# module.net
KiCad netlist of a schematic drawn in EAGLE
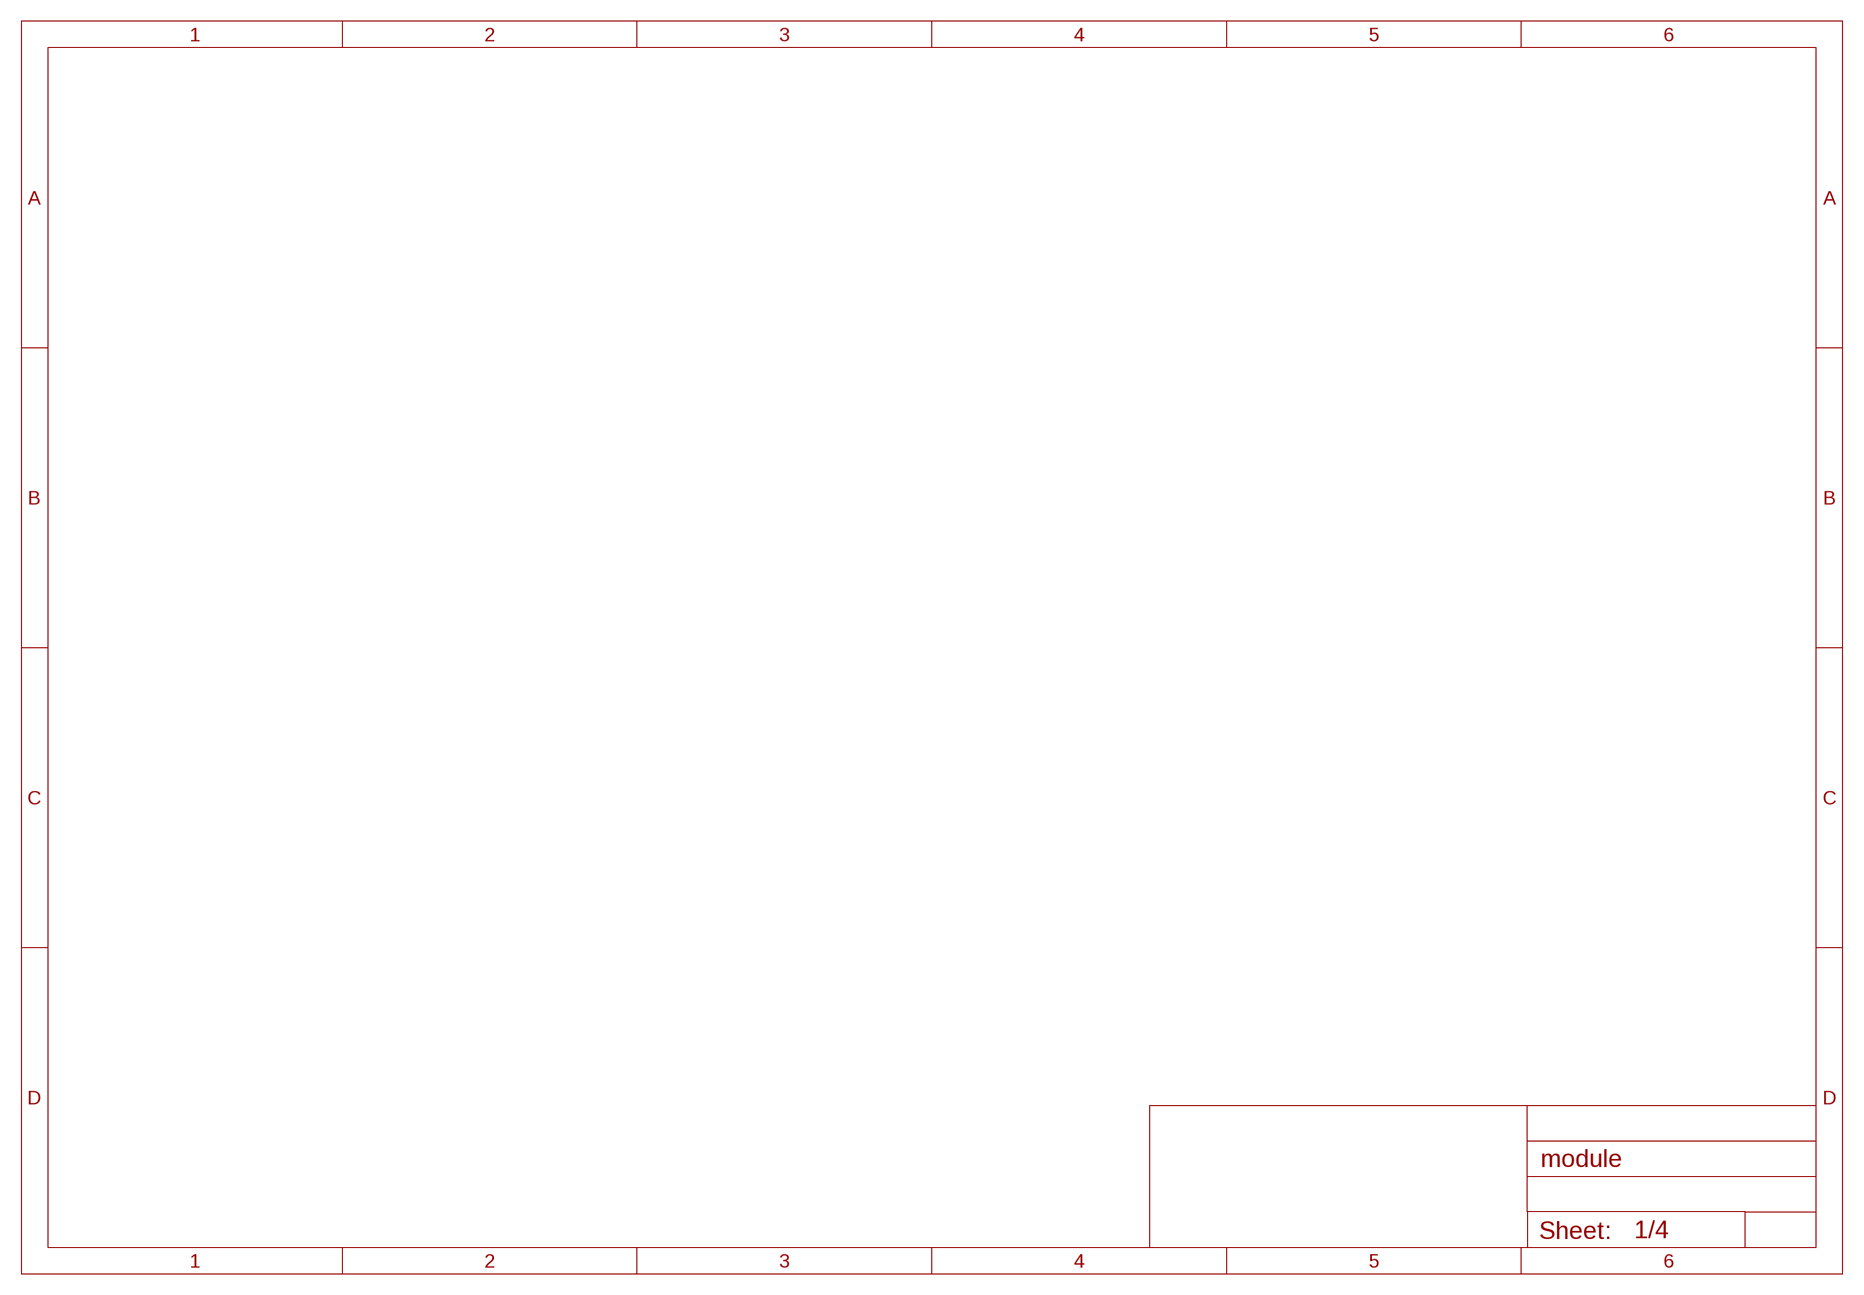
[diagram p0: schematic, sheet 1]
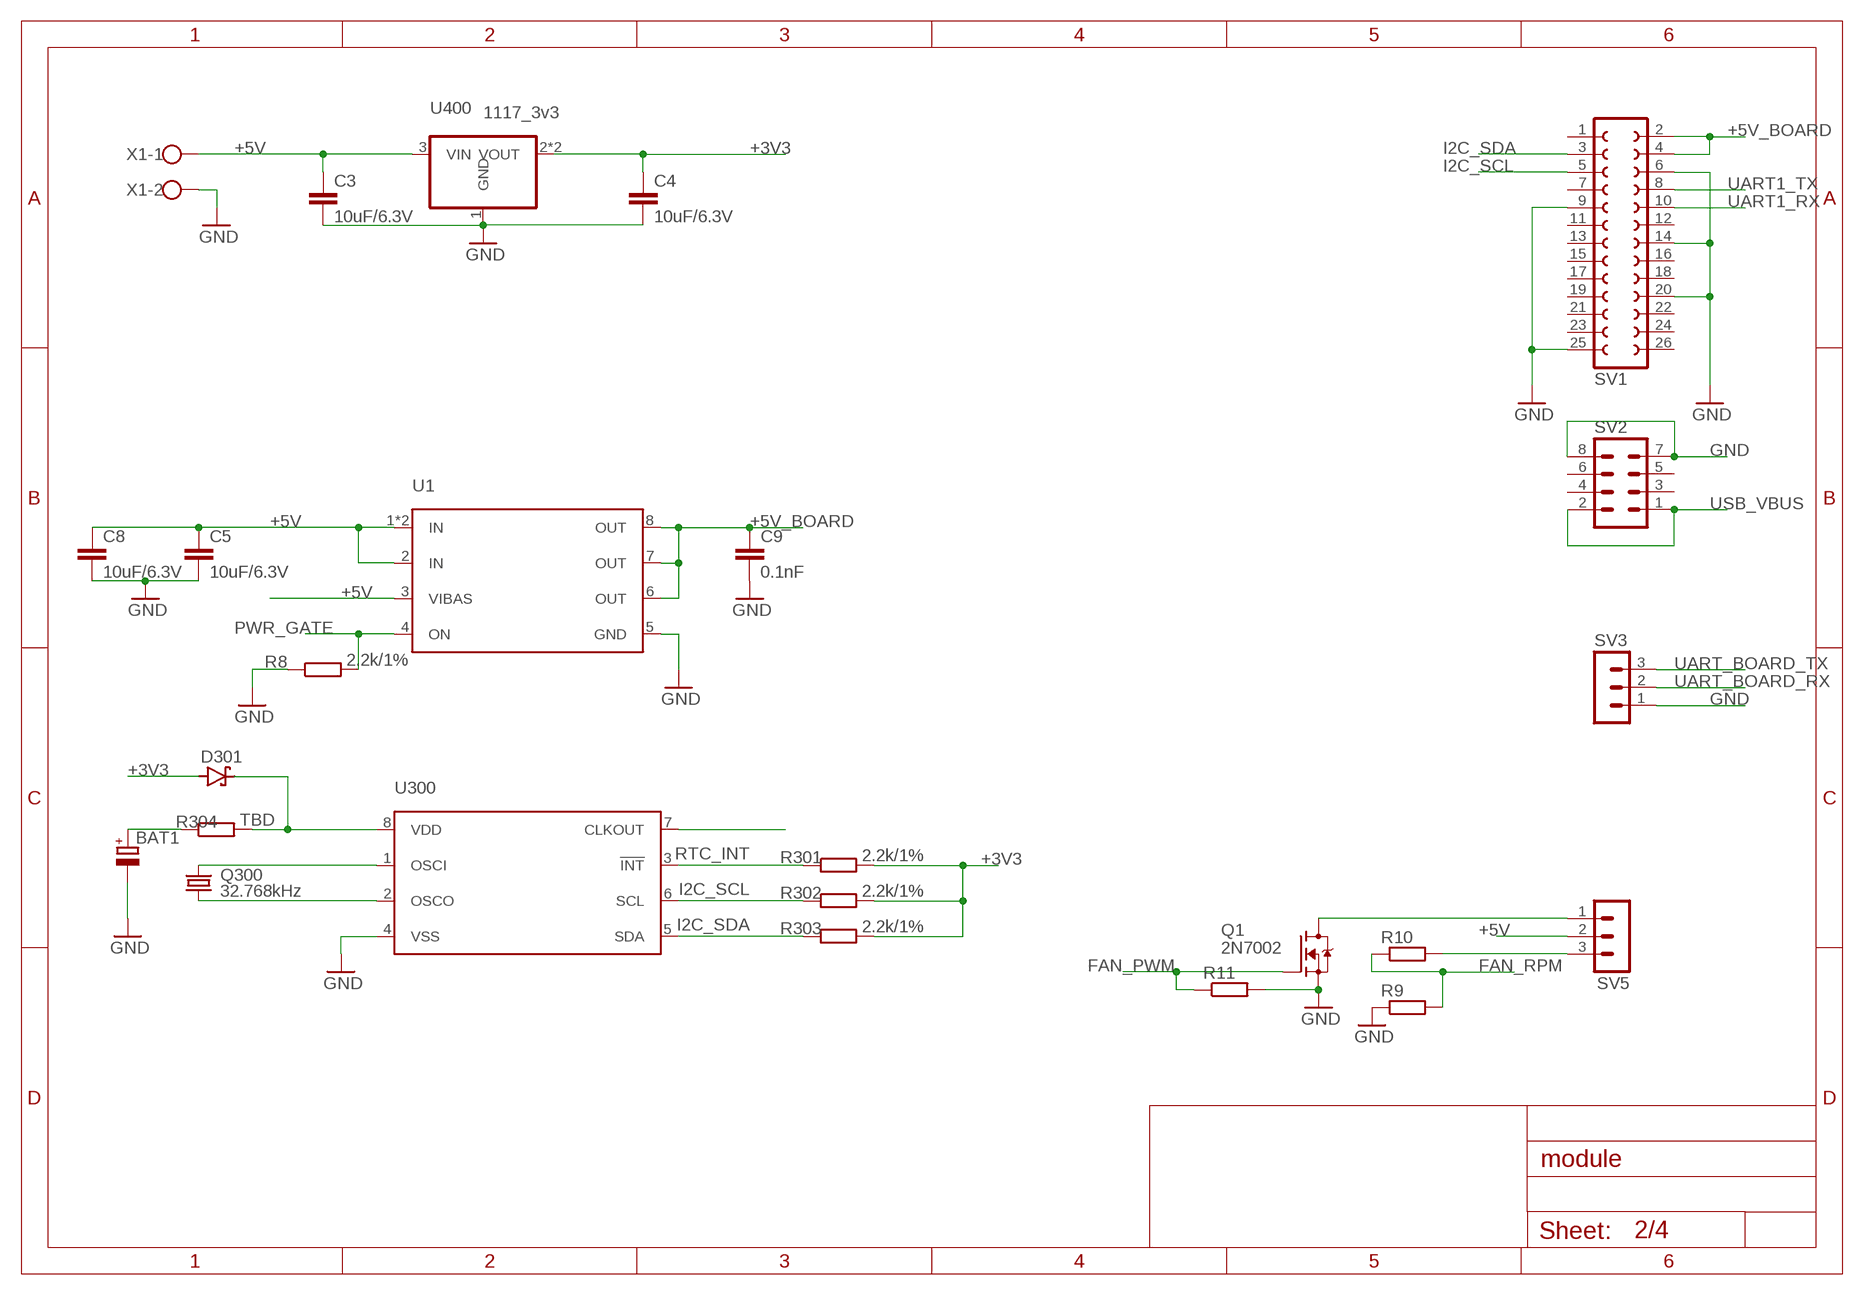
[diagram p1: schematic, sheet 2]
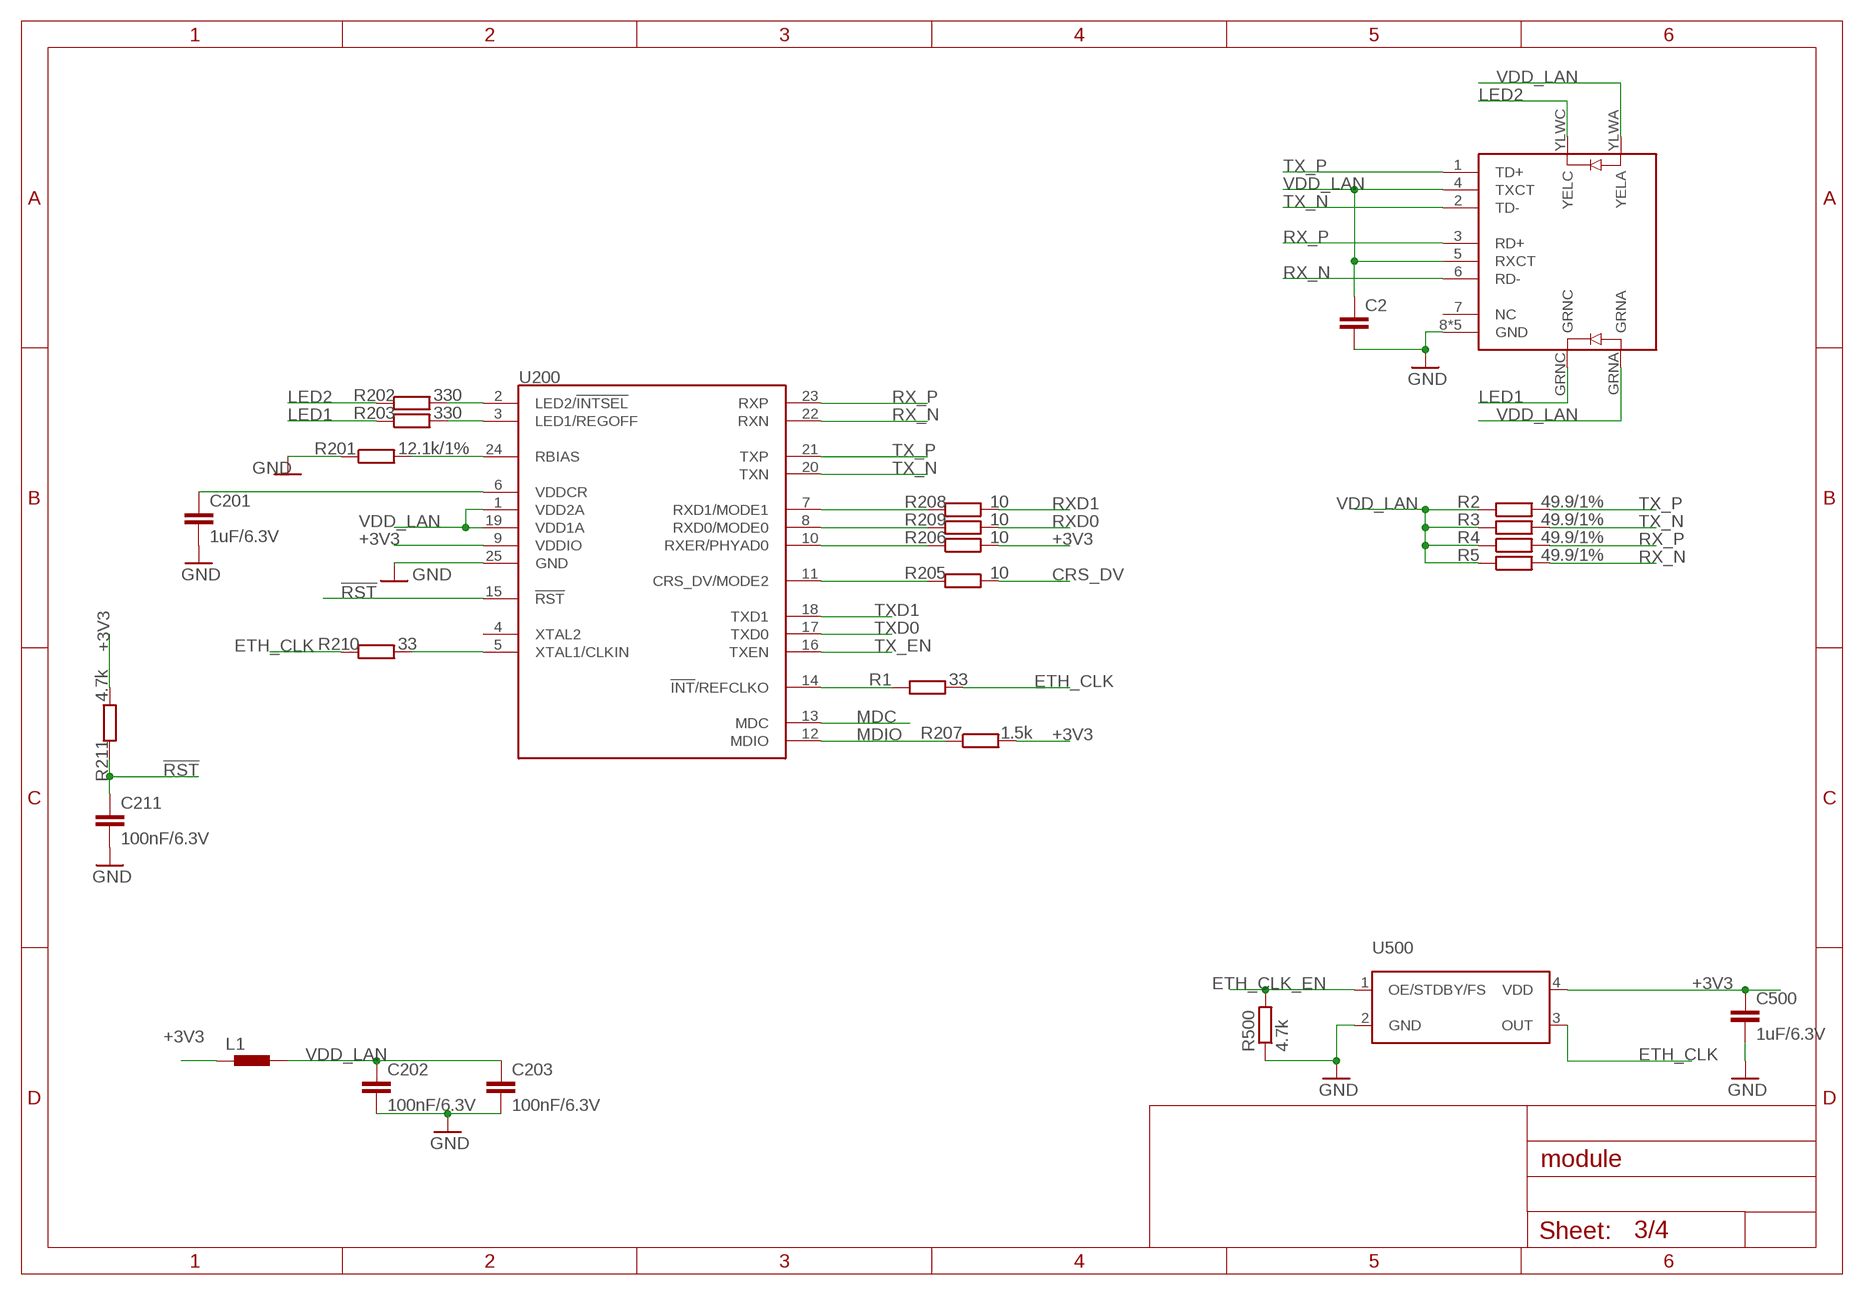
[diagram p2: schematic, sheet 3]
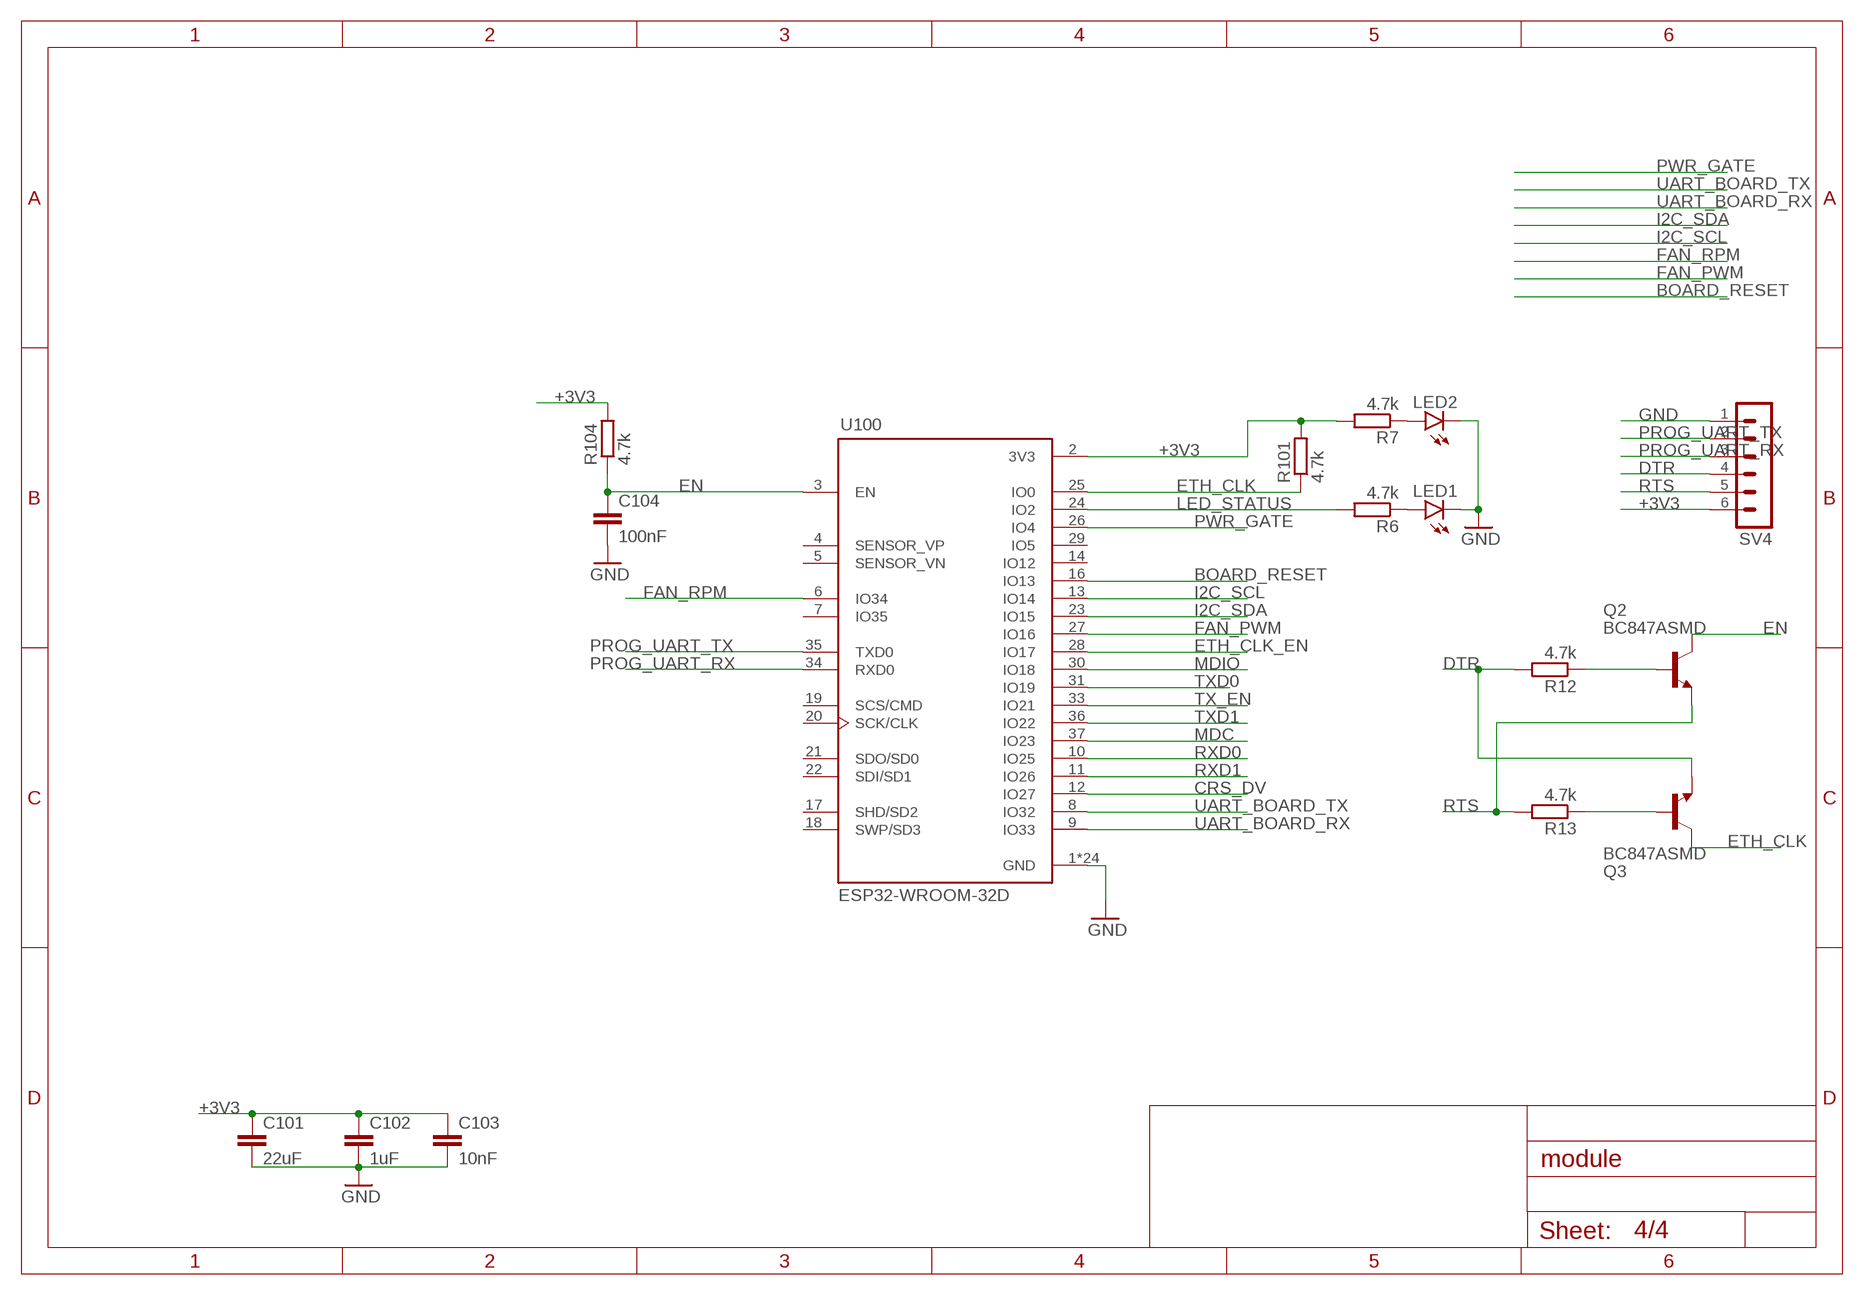
[diagram p3: schematic, sheet 4]

(export (version "E")
  (design (tool "Eeschema 10.0.6"))
  (components
    (comp (ref "BAT1")
      (value "DCK-3R3E224U-E")
      (footprint "eagle-import:621")
      (libsource (lib "eagle-import") (part "DCK-3R3E224U-E"))
    )
    (comp (ref "C3")
      (value "10uF/6.3V")
      (footprint "eagle-import:C1206")
      (libsource (lib "eagle-import") (part "C-EUC1206"))
    )
    (comp (ref "C4")
      (value "10uF/6.3V")
      (footprint "eagle-import:C1206")
      (libsource (lib "eagle-import") (part "C-EUC1206"))
    )
    (comp (ref "C5")
      (value "10uF/6.3V")
      (footprint "eagle-import:C0603")
      (libsource (lib "eagle-import") (part "C-EUC0603"))
    )
    (comp (ref "C8")
      (value "10uF/6.3V")
      (footprint "eagle-import:C0603")
      (libsource (lib "eagle-import") (part "C-EUC0603"))
    )
    (comp (ref "C9")
      (value "0.1nF")
      (footprint "eagle-import:C0603")
      (libsource (lib "eagle-import") (part "C-EUC0603"))
    )
    (comp (ref "D301")
      (value "NSR0320")
      (footprint "eagle-import:SOD323")
      (libsource (lib "eagle-import") (part "NSR0320"))
    )
    (comp (ref "Q1")
      (value "2N7002")
      (footprint "eagle-import:SOT95P240X110-3")
      (libsource (lib "eagle-import") (part "2N7002"))
    )
    (comp (ref "Q300")
      (value "32.768kHz")
      (footprint "eagle-import:3215")
      (libsource (lib "eagle-import") (part "CFPX–217-NHT"))
    )
    (comp (ref "R8")
      (value "2.2k/1%")
      (footprint "eagle-import:R0603")
      (libsource (lib "eagle-import") (part "R-EU_R0603"))
    )
    (comp (ref "R9")
      (value "R-EU_R0603")
      (footprint "eagle-import:R0603")
      (libsource (lib "eagle-import") (part "R-EU_R0603"))
    )
    (comp (ref "R10")
      (value "R-EU_R0603")
      (footprint "eagle-import:R0603")
      (libsource (lib "eagle-import") (part "R-EU_R0603"))
    )
    (comp (ref "R11")
      (value "R-EU_R0603")
      (footprint "eagle-import:R0603")
      (libsource (lib "eagle-import") (part "R-EU_R0603"))
    )
    (comp (ref "R301")
      (value "2.2k/1%")
      (footprint "eagle-import:R0603")
      (libsource (lib "eagle-import") (part "R-EU_R0603"))
    )
    (comp (ref "R302")
      (value "2.2k/1%")
      (footprint "eagle-import:R0603")
      (libsource (lib "eagle-import") (part "R-EU_R0603"))
    )
    (comp (ref "R303")
      (value "2.2k/1%")
      (footprint "eagle-import:R0603")
      (libsource (lib "eagle-import") (part "R-EU_R0603"))
    )
    (comp (ref "R304")
      (value "TBD")
      (footprint "eagle-import:R0603")
      (libsource (lib "eagle-import") (part "R-EU_R0603"))
    )
    (comp (ref "SV1")
      (value "FE13-2")
      (footprint "eagle-import:FE13-2")
      (libsource (lib "eagle-import") (part "FE13-2"))
    )
    (comp (ref "SV2")
      (value "MA04-2")
      (footprint "eagle-import:MA04-2")
      (libsource (lib "eagle-import") (part "MA04-2"))
    )
    (comp (ref "SV3")
      (value "MA03-1FEMALE")
      (footprint "eagle-import:MA03-1")
      (libsource (lib "eagle-import") (part "MA03-1FEMALE"))
    )
    (comp (ref "SV5")
      (value "MA03-1")
      (footprint "eagle-import:MA03-1")
      (libsource (lib "eagle-import") (part "MA03-1"))
    )
    (comp (ref "U1")
      (value "DML10M8LDS")
      (footprint "eagle-import:SON65P300X300X80-9T160X240N")
      (libsource (lib "eagle-import") (part "DML10M8LDS"))
    )
    (comp (ref "U300")
      (value "PCF85063ATT")
      (footprint "eagle-import:SOP65P490X110-8N")
      (libsource (lib "eagle-import") (part "PCF85063ATT"))
    )
    (comp (ref "U400")
      (value "1117_3v3")
      (footprint "eagle-import:SOT230P700X180-4")
      (libsource (lib "eagle-import") (part "LD1117S50"))
    )
    (comp (ref "X1")
      (value "W237-102")
      (footprint "eagle-import:EBBA")
      (libsource (lib "eagle-import") (part "W237-102"))
    )
    (comp (ref "C2")
      (value "C-EUC0603")
      (footprint "eagle-import:C0603")
      (libsource (lib "eagle-import") (part "C-EUC0603"))
    )
    (comp (ref "C201")
      (value "1uF/6.3V")
      (footprint "eagle-import:C0603")
      (libsource (lib "eagle-import") (part "C-EUC0603"))
    )
    (comp (ref "C202")
      (value "100nF/6.3V")
      (footprint "eagle-import:C0603")
      (libsource (lib "eagle-import") (part "C-EUC0603"))
    )
    (comp (ref "C203")
      (value "100nF/6.3V")
      (footprint "eagle-import:C0603")
      (libsource (lib "eagle-import") (part "C-EUC0603"))
    )
    (comp (ref "C211")
      (value "100nF/6.3V")
      (footprint "eagle-import:C0603")
      (libsource (lib "eagle-import") (part "C-EUC0603"))
    )
    (comp (ref "C500")
      (value "1uF/6.3V")
      (footprint "eagle-import:C0603")
      (libsource (lib "eagle-import") (part "C-EUC0603"))
    )
    (comp (ref "J1")
      (value "ARJM11X1009XXXXX")
      (footprint "eagle-import:LAYOUT1-HORIZ-LEDS")
      (libsource (lib "eagle-import") (part "ARJM11X1009XXXXX"))
    )
    (comp (ref "L1")
      (value "FER-0603")
      (footprint "eagle-import:FER0603")
      (libsource (lib "eagle-import") (part "FER-0603"))
    )
    (comp (ref "R1")
      (value "33")
      (footprint "eagle-import:R0603")
      (libsource (lib "eagle-import") (part "R-EU_R0603"))
    )
    (comp (ref "R2")
      (value "49.9/1%")
      (footprint "eagle-import:R0603")
      (libsource (lib "eagle-import") (part "R-EU_R0603"))
    )
    (comp (ref "R3")
      (value "49.9/1%")
      (footprint "eagle-import:R0603")
      (libsource (lib "eagle-import") (part "R-EU_R0603"))
    )
    (comp (ref "R4")
      (value "49.9/1%")
      (footprint "eagle-import:R0603")
      (libsource (lib "eagle-import") (part "R-EU_R0603"))
    )
    (comp (ref "R5")
      (value "49.9/1%")
      (footprint "eagle-import:R0603")
      (libsource (lib "eagle-import") (part "R-EU_R0603"))
    )
    (comp (ref "R201")
      (value "12.1k/1%")
      (footprint "eagle-import:R0603")
      (libsource (lib "eagle-import") (part "R-EU_R0603"))
    )
    (comp (ref "R202")
      (value "330")
      (footprint "eagle-import:R0603")
      (libsource (lib "eagle-import") (part "R-EU_R0603"))
    )
    (comp (ref "R203")
      (value "330")
      (footprint "eagle-import:R0603")
      (libsource (lib "eagle-import") (part "R-EU_R0603"))
    )
    (comp (ref "R205")
      (value "10")
      (footprint "eagle-import:R0603")
      (libsource (lib "eagle-import") (part "R-EU_R0603"))
    )
    (comp (ref "R206")
      (value "10")
      (footprint "eagle-import:R0603")
      (libsource (lib "eagle-import") (part "R-EU_R0603"))
    )
    (comp (ref "R207")
      (value "1.5k")
      (footprint "eagle-import:R0603")
      (libsource (lib "eagle-import") (part "R-EU_R0603"))
    )
    (comp (ref "R208")
      (value "10")
      (footprint "eagle-import:R0603")
      (libsource (lib "eagle-import") (part "R-EU_R0603"))
    )
    (comp (ref "R209")
      (value "10")
      (footprint "eagle-import:R0603")
      (libsource (lib "eagle-import") (part "R-EU_R0603"))
    )
    (comp (ref "R210")
      (value "33")
      (footprint "eagle-import:R0603")
      (libsource (lib "eagle-import") (part "R-EU_R0603"))
    )
    (comp (ref "R211")
      (value "4.7k")
      (footprint "eagle-import:R0603")
      (libsource (lib "eagle-import") (part "R-EU_R0603"))
    )
    (comp (ref "R500")
      (value "4.7k")
      (footprint "eagle-import:R0603")
      (libsource (lib "eagle-import") (part "R-EU_R0603"))
    )
    (comp (ref "U200")
      (value "LAN8720A")
      (footprint "eagle-import:QFN50P400X400X100-25T250N")
      (libsource (lib "eagle-import") (part "LAN8720A"))
    )
    (comp (ref "U500")
      (value "DSC61XXC")
      (footprint "eagle-import:DIODFN250X200X89-4N")
      (libsource (lib "eagle-import") (part "DSC61XXC"))
    )
    (comp (ref "C101")
      (value "22uF")
      (footprint "eagle-import:C1206")
      (libsource (lib "eagle-import") (part "C-EUC1206"))
    )
    (comp (ref "C102")
      (value "1uF")
      (footprint "eagle-import:C0603")
      (libsource (lib "eagle-import") (part "C-EUC0603"))
    )
    (comp (ref "C103")
      (value "10nF")
      (footprint "eagle-import:C0603")
      (libsource (lib "eagle-import") (part "C-EUC0603"))
    )
    (comp (ref "C104")
      (value "100nF")
      (footprint "eagle-import:C0603")
      (libsource (lib "eagle-import") (part "C-EUC0603"))
    )
    (comp (ref "LED1")
      (value "LEDCHIP-LED0805")
      (footprint "eagle-import:CHIP-LED0805")
      (libsource (lib "eagle-import") (part "LEDCHIP-LED0805"))
    )
    (comp (ref "LED2")
      (value "LEDCHIP-LED0805")
      (footprint "eagle-import:CHIP-LED0805")
      (libsource (lib "eagle-import") (part "LEDCHIP-LED0805"))
    )
    (comp (ref "Q2")
      (value "BC847ASMD")
      (footprint "eagle-import:SOT23")
      (libsource (lib "eagle-import") (part "BC847SMDA"))
    )
    (comp (ref "Q3")
      (value "BC847ASMD")
      (footprint "eagle-import:SOT23")
      (libsource (lib "eagle-import") (part "BC847SMDA"))
    )
    (comp (ref "R6")
      (value "4.7k")
      (footprint "eagle-import:R0603")
      (libsource (lib "eagle-import") (part "R-EU_R0603"))
    )
    (comp (ref "R7")
      (value "4.7k")
      (footprint "eagle-import:R0603")
      (libsource (lib "eagle-import") (part "R-EU_R0603"))
    )
    (comp (ref "R12")
      (value "4.7k")
      (footprint "eagle-import:R0603")
      (libsource (lib "eagle-import") (part "R-EU_R0603"))
    )
    (comp (ref "R13")
      (value "4.7k")
      (footprint "eagle-import:R0603")
      (libsource (lib "eagle-import") (part "R-EU_R0603"))
    )
    (comp (ref "R101")
      (value "4.7k")
      (footprint "eagle-import:R0603")
      (libsource (lib "eagle-import") (part "R-EU_R0603"))
    )
    (comp (ref "R104")
      (value "4.7k")
      (footprint "eagle-import:R0603")
      (libsource (lib "eagle-import") (part "R-EU_R0603"))
    )
    (comp (ref "SV4")
      (value "CONN-1X6")
      (footprint "eagle-import:MA06-1")
      (libsource (lib "eagle-import") (part "CONN-1X6"))
    )
    (comp (ref "U100")
      (value "ESP32-WROOM-32D")
      (footprint "eagle-import:MODULE_ESP32-WROOM-32D")
      (fields (field (name "MF") "Espressif Systems"))
      (libsource (lib "eagle-import") (part "ESP32-WROOM-32D"))
    )
  )
  (nets
    (net (code "1") (name "+3V3") (class "Default")
      (node (ref "C101") (pin "1") (pinfunction "1_1") (pintype "passive"))
      (node (ref "C102") (pin "1") (pinfunction "1_1") (pintype "passive"))
      (node (ref "C103") (pin "1") (pinfunction "1_1") (pintype "passive"))
      (node (ref "C4") (pin "1") (pinfunction "1_1") (pintype "passive"))
      (node (ref "C500") (pin "1") (pinfunction "1_1") (pintype "passive"))
      (node (ref "D301") (pin "A") (pinfunction "A_A") (pintype "passive"))
      (node (ref "L1") (pin "1") (pinfunction "1_1") (pintype "passive"))
      (node (ref "R101") (pin "2") (pinfunction "2_2") (pintype "passive"))
      (node (ref "R104") (pin "2") (pinfunction "2_2") (pintype "passive"))
      (node (ref "R206") (pin "2") (pinfunction "2_2") (pintype "passive"))
      (node (ref "R207") (pin "2") (pinfunction "2_2") (pintype "passive"))
      (node (ref "R211") (pin "2") (pinfunction "2_2") (pintype "passive"))
      (node (ref "R301") (pin "2") (pinfunction "2_2") (pintype "passive"))
      (node (ref "R302") (pin "2") (pinfunction "2_2") (pintype "passive"))
      (node (ref "R303") (pin "2") (pinfunction "2_2") (pintype "passive"))
      (node (ref "R7") (pin "2") (pinfunction "2_2") (pintype "passive"))
      (node (ref "SV4") (pin "6") (pinfunction "6_6") (pintype "passive"))
      (node (ref "U100") (pin "2") (pinfunction "3V3_2") (pintype "power_in"))
      (node (ref "U200") (pin "9") (pinfunction "VDDIO_9") (pintype "bidirectional"))
      (node (ref "U400") (pin "2") (pinfunction "VOUT_2") (pintype "output"))
      (node (ref "U400") (pin "4") (pinfunction "VOUT_4") (pintype "output"))
      (node (ref "U500") (pin "4") (pinfunction "VDD_4") (pintype "bidirectional"))
    )
    (net (code "2") (name "+5V") (class "Default")
      (node (ref "C3") (pin "1") (pinfunction "1_1") (pintype "passive"))
      (node (ref "C5") (pin "1") (pinfunction "1_1") (pintype "passive"))
      (node (ref "C8") (pin "1") (pinfunction "1_1") (pintype "passive"))
      (node (ref "SV5") (pin "2") (pinfunction "2_2") (pintype "passive"))
      (node (ref "U1") (pin "1") (pinfunction "IN_1") (pintype "bidirectional"))
      (node (ref "U1") (pin "2") (pinfunction "IN_2") (pintype "bidirectional"))
      (node (ref "U1") (pin "3") (pinfunction "VIBAS_3") (pintype "bidirectional"))
      (node (ref "U1") (pin "9") (pinfunction "IN_9") (pintype "bidirectional"))
      (node (ref "U400") (pin "3") (pinfunction "VIN_3") (pintype "input"))
      (node (ref "X1") (pin "1") (pinfunction "KL_1") (pintype "passive"))
    )
    (net (code "3") (name "+5V_BOARD") (class "Default")
      (node (ref "C9") (pin "1") (pinfunction "1_1") (pintype "passive"))
      (node (ref "SV1") (pin "2") (pinfunction "2_2") (pintype "passive"))
      (node (ref "SV1") (pin "4") (pinfunction "4_4") (pintype "passive"))
      (node (ref "U1") (pin "6") (pinfunction "OUT_6") (pintype "bidirectional"))
      (node (ref "U1") (pin "7") (pinfunction "OUT_7") (pintype "bidirectional"))
      (node (ref "U1") (pin "8") (pinfunction "OUT_8") (pintype "bidirectional"))
    )
    (net (code "4") (name "BOARD_RESET") (class "Default")
      (node (ref "U100") (pin "16") (pinfunction "IO13_16") (pintype "bidirectional"))
    )
    (net (code "5") (name "CRS_DV") (class "Default")
      (node (ref "R205") (pin "2") (pinfunction "2_2") (pintype "passive"))
      (node (ref "U100") (pin "12") (pinfunction "IO27_12") (pintype "bidirectional"))
    )
    (net (code "6") (name "DTR") (class "Default")
      (node (ref "Q3") (pin "2") (pinfunction "E_2") (pintype "passive"))
      (node (ref "R12") (pin "2") (pinfunction "2_2") (pintype "passive"))
      (node (ref "SV4") (pin "4") (pinfunction "4_4") (pintype "passive"))
    )
    (net (code "7") (name "EN") (class "Default")
      (node (ref "C104") (pin "1") (pinfunction "1_1") (pintype "passive"))
      (node (ref "Q2") (pin "3") (pinfunction "C_3") (pintype "passive"))
      (node (ref "R104") (pin "1") (pinfunction "1_1") (pintype "passive"))
      (node (ref "U100") (pin "3") (pinfunction "EN_3") (pintype "input"))
    )
    (net (code "8") (name "ETH_CLK") (class "Default")
      (node (ref "Q3") (pin "3") (pinfunction "C_3") (pintype "passive"))
      (node (ref "R1") (pin "2") (pinfunction "2_2") (pintype "passive"))
      (node (ref "R101") (pin "1") (pinfunction "1_1") (pintype "passive"))
      (node (ref "R210") (pin "1") (pinfunction "1_1") (pintype "passive"))
      (node (ref "U100") (pin "25") (pinfunction "IO0_25") (pintype "bidirectional"))
      (node (ref "U500") (pin "3") (pinfunction "OUT_3") (pintype "bidirectional"))
    )
    (net (code "9") (name "ETH_CLK_EN") (class "Default")
      (node (ref "R500") (pin "2") (pinfunction "2_2") (pintype "passive"))
      (node (ref "U100") (pin "28") (pinfunction "IO17_28") (pintype "bidirectional"))
      (node (ref "U500") (pin "1") (pinfunction "OE/STDBY/FS_1") (pintype "bidirectional"))
    )
    (net (code "10") (name "FAN_PWM") (class "Default")
      (node (ref "Q1") (pin "1") (pinfunction "G_1") (pintype "passive"))
      (node (ref "R11") (pin "1") (pinfunction "1_1") (pintype "passive"))
      (node (ref "U100") (pin "27") (pinfunction "IO16_27") (pintype "bidirectional"))
    )
    (net (code "11") (name "FAN_RPM") (class "Default")
      (node (ref "R10") (pin "1") (pinfunction "1_1") (pintype "passive"))
      (node (ref "R9") (pin "2") (pinfunction "2_2") (pintype "passive"))
      (node (ref "U100") (pin "6") (pinfunction "IO34_6") (pintype "input"))
    )
    (net (code "12") (name "GND") (class "Default")
      (node (ref "BAT1") (pin "-") (pinfunction "-_-") (pintype "passive"))
      (node (ref "C101") (pin "2") (pinfunction "2_2") (pintype "passive"))
      (node (ref "C102") (pin "2") (pinfunction "2_2") (pintype "passive"))
      (node (ref "C103") (pin "2") (pinfunction "2_2") (pintype "passive"))
      (node (ref "C104") (pin "2") (pinfunction "2_2") (pintype "passive"))
      (node (ref "C2") (pin "2") (pinfunction "2_2") (pintype "passive"))
      (node (ref "C201") (pin "2") (pinfunction "2_2") (pintype "passive"))
      (node (ref "C202") (pin "2") (pinfunction "2_2") (pintype "passive"))
      (node (ref "C203") (pin "2") (pinfunction "2_2") (pintype "passive"))
      (node (ref "C211") (pin "2") (pinfunction "2_2") (pintype "passive"))
      (node (ref "C3") (pin "2") (pinfunction "2_2") (pintype "passive"))
      (node (ref "C4") (pin "2") (pinfunction "2_2") (pintype "passive"))
      (node (ref "C5") (pin "2") (pinfunction "2_2") (pintype "passive"))
      (node (ref "C500") (pin "2") (pinfunction "2_2") (pintype "passive"))
      (node (ref "C8") (pin "2") (pinfunction "2_2") (pintype "passive"))
      (node (ref "C9") (pin "2") (pinfunction "2_2") (pintype "passive"))
      (node (ref "J1") (pin "8") (pinfunction "GND_8") (pintype "bidirectional"))
      (node (ref "J1") (pin "P$1") (pinfunction "GND_P$1") (pintype "bidirectional"))
      (node (ref "J1") (pin "P$2") (pinfunction "GND_P$2") (pintype "bidirectional"))
      (node (ref "J1") (pin "P$3") (pinfunction "GND_P$3") (pintype "bidirectional"))
      (node (ref "J1") (pin "P$4") (pinfunction "GND_P$4") (pintype "bidirectional"))
      (node (ref "LED1") (pin "C") (pinfunction "C_C") (pintype "passive"))
      (node (ref "LED2") (pin "C") (pinfunction "C_C") (pintype "passive"))
      (node (ref "Q1") (pin "2") (pinfunction "S_2") (pintype "passive"))
      (node (ref "R11") (pin "2") (pinfunction "2_2") (pintype "passive"))
      (node (ref "R201") (pin "1") (pinfunction "1_1") (pintype "passive"))
      (node (ref "R500") (pin "1") (pinfunction "1_1") (pintype "passive"))
      (node (ref "R8") (pin "1") (pinfunction "1_1") (pintype "passive"))
      (node (ref "R9") (pin "1") (pinfunction "1_1") (pintype "passive"))
      (node (ref "SV1") (pin "14") (pinfunction "14_14") (pintype "passive"))
      (node (ref "SV1") (pin "20") (pinfunction "20_20") (pintype "passive"))
      (node (ref "SV1") (pin "25") (pinfunction "25_25") (pintype "passive"))
      (node (ref "SV1") (pin "6") (pinfunction "6_6") (pintype "passive"))
      (node (ref "SV1") (pin "9") (pinfunction "9_9") (pintype "passive"))
      (node (ref "SV2") (pin "7") (pinfunction "7_7") (pintype "passive"))
      (node (ref "SV2") (pin "8") (pinfunction "8_8") (pintype "passive"))
      (node (ref "SV3") (pin "1") (pinfunction "1_1") (pintype "passive"))
      (node (ref "SV4") (pin "1") (pinfunction "1_1") (pintype "passive"))
      (node (ref "U1") (pin "5") (pinfunction "GND_5") (pintype "bidirectional"))
      (node (ref "U100") (pin "1") (pinfunction "GND_1") (pintype "power_in"))
      (node (ref "U100") (pin "15") (pinfunction "GND_15") (pintype "power_in"))
      (node (ref "U100") (pin "38") (pinfunction "GND_38") (pintype "power_in"))
      (node (ref "U100") (pin "39_1") (pinfunction "GND_39_1") (pintype "power_in"))
      (node (ref "U100") (pin "39_10") (pinfunction "GND_39_10") (pintype "power_in"))
      (node (ref "U100") (pin "39_11") (pinfunction "GND_39_11") (pintype "power_in"))
      (node (ref "U100") (pin "39_12") (pinfunction "GND_39_12") (pintype "power_in"))
      (node (ref "U100") (pin "39_13") (pinfunction "GND_39_13") (pintype "power_in"))
      (node (ref "U100") (pin "39_14") (pinfunction "GND_39_14") (pintype "power_in"))
      (node (ref "U100") (pin "39_15") (pinfunction "GND_39_15") (pintype "power_in"))
      (node (ref "U100") (pin "39_16") (pinfunction "GND_39_16") (pintype "power_in"))
      (node (ref "U100") (pin "39_17") (pinfunction "GND_39_17") (pintype "power_in"))
      (node (ref "U100") (pin "39_18") (pinfunction "GND_39_18") (pintype "power_in"))
      (node (ref "U100") (pin "39_19") (pinfunction "GND_39_19") (pintype "power_in"))
      (node (ref "U100") (pin "39_2") (pinfunction "GND_39_2") (pintype "power_in"))
      (node (ref "U100") (pin "39_20") (pinfunction "GND_39_20") (pintype "power_in"))
      (node (ref "U100") (pin "39_21") (pinfunction "GND_39_21") (pintype "power_in"))
      (node (ref "U100") (pin "39_3") (pinfunction "GND_39_3") (pintype "power_in"))
      (node (ref "U100") (pin "39_4") (pinfunction "GND_39_4") (pintype "power_in"))
      (node (ref "U100") (pin "39_5") (pinfunction "GND_39_5") (pintype "power_in"))
      (node (ref "U100") (pin "39_6") (pinfunction "GND_39_6") (pintype "power_in"))
      (node (ref "U100") (pin "39_7") (pinfunction "GND_39_7") (pintype "power_in"))
      (node (ref "U100") (pin "39_8") (pinfunction "GND_39_8") (pintype "power_in"))
      (node (ref "U100") (pin "39_9") (pinfunction "GND_39_9") (pintype "power_in"))
      (node (ref "U200") (pin "25") (pinfunction "GND_25") (pintype "bidirectional"))
      (node (ref "U300") (pin "4") (pinfunction "VSS_4") (pintype "bidirectional"))
      (node (ref "U400") (pin "1") (pinfunction "GND_1") (pintype "power_in"))
      (node (ref "U500") (pin "2") (pinfunction "GND_2") (pintype "bidirectional"))
      (node (ref "X1") (pin "2") (pinfunction "KL_2") (pintype "passive"))
    )
    (net (code "13") (name "I2C_SCL") (class "Default")
      (node (ref "R302") (pin "1") (pinfunction "1_1") (pintype "passive"))
      (node (ref "SV1") (pin "5") (pinfunction "5_5") (pintype "passive"))
      (node (ref "U100") (pin "13") (pinfunction "IO14_13") (pintype "bidirectional"))
      (node (ref "U300") (pin "6") (pinfunction "SCL_6") (pintype "bidirectional"))
    )
    (net (code "14") (name "I2C_SDA") (class "Default")
      (node (ref "R303") (pin "1") (pinfunction "1_1") (pintype "passive"))
      (node (ref "SV1") (pin "3") (pinfunction "3_3") (pintype "passive"))
      (node (ref "U100") (pin "23") (pinfunction "IO15_23") (pintype "bidirectional"))
      (node (ref "U300") (pin "5") (pinfunction "SDA_5") (pintype "bidirectional"))
    )
    (net (code "15") (name "LED1") (class "Default")
      (node (ref "J1") (pin "GRNC") (pinfunction "GRNC_GRNC") (pintype "bidirectional"))
      (node (ref "R203") (pin "1") (pinfunction "1_1") (pintype "passive"))
    )
    (net (code "16") (name "LED2") (class "Default")
      (node (ref "J1") (pin "YLWC") (pinfunction "YELC_YLWC") (pintype "bidirectional"))
      (node (ref "R202") (pin "1") (pinfunction "1_1") (pintype "passive"))
    )
    (net (code "17") (name "LED_STATUS") (class "Default")
      (node (ref "R6") (pin "2") (pinfunction "2_2") (pintype "passive"))
      (node (ref "U100") (pin "24") (pinfunction "IO2_24") (pintype "bidirectional"))
    )
    (net (code "18") (name "MDC") (class "Default")
      (node (ref "U100") (pin "37") (pinfunction "IO23_37") (pintype "bidirectional"))
      (node (ref "U200") (pin "13") (pinfunction "MDC_13") (pintype "bidirectional"))
    )
    (net (code "19") (name "MDIO") (class "Default")
      (node (ref "R207") (pin "1") (pinfunction "1_1") (pintype "passive"))
      (node (ref "U100") (pin "30") (pinfunction "IO18_30") (pintype "bidirectional"))
      (node (ref "U200") (pin "12") (pinfunction "MDIO_12") (pintype "bidirectional"))
    )
    (net (code "20") (name "Net-(BAT1-Pad+)") (class "Default")
      (node (ref "BAT1") (pin "+") (pinfunction "+_+") (pintype "passive"))
      (node (ref "R304") (pin "1") (pinfunction "1_1") (pintype "passive"))
    )
    (net (code "21") (name "Net-(D301-C)") (class "Default")
      (node (ref "D301") (pin "K") (pinfunction "C_K") (pintype "passive"))
      (node (ref "R304") (pin "2") (pinfunction "2_2") (pintype "passive"))
      (node (ref "U300") (pin "8") (pinfunction "VDD_8") (pintype "bidirectional"))
    )
    (net (code "22") (name "Net-(LED1-PadA)") (class "Default")
      (node (ref "LED1") (pin "A") (pinfunction "A_A") (pintype "passive"))
      (node (ref "R6") (pin "1") (pinfunction "1_1") (pintype "passive"))
    )
    (net (code "23") (name "Net-(LED2-PadA)") (class "Default")
      (node (ref "LED2") (pin "A") (pinfunction "A_A") (pintype "passive"))
      (node (ref "R7") (pin "1") (pinfunction "1_1") (pintype "passive"))
    )
    (net (code "24") (name "Net-(Q1-D)") (class "Default")
      (node (ref "Q1") (pin "3") (pinfunction "D_3") (pintype "passive"))
      (node (ref "SV5") (pin "1") (pinfunction "1_1") (pintype "passive"))
    )
    (net (code "25") (name "Net-(Q2-B)") (class "Default")
      (node (ref "Q2") (pin "1") (pinfunction "B_1") (pintype "passive"))
      (node (ref "R12") (pin "1") (pinfunction "1_1") (pintype "passive"))
    )
    (net (code "26") (name "Net-(Q3-B)") (class "Default")
      (node (ref "Q3") (pin "1") (pinfunction "B_1") (pintype "passive"))
      (node (ref "R13") (pin "1") (pinfunction "1_1") (pintype "passive"))
    )
    (net (code "27") (name "Net-(R10-Pad2)") (class "Default")
      (node (ref "R10") (pin "2") (pinfunction "2_2") (pintype "passive"))
      (node (ref "SV5") (pin "3") (pinfunction "3_3") (pintype "passive"))
    )
    (net (code "28") (name "Net-(U200-CRS_DV{slash}MODE2)") (class "Default")
      (node (ref "R205") (pin "1") (pinfunction "1_1") (pintype "passive"))
      (node (ref "U200") (pin "11") (pinfunction "CRS_DV/MODE2_11") (pintype "bidirectional"))
    )
    (net (code "29") (name "Net-(U200-LED1{slash}REGOFF)") (class "Default")
      (node (ref "R203") (pin "2") (pinfunction "2_2") (pintype "passive"))
      (node (ref "U200") (pin "3") (pinfunction "LED1/REGOFF_3") (pintype "bidirectional"))
    )
    (net (code "30") (name "Net-(U200-LED2{slash}~{INTSEL})") (class "Default")
      (node (ref "R202") (pin "2") (pinfunction "2_2") (pintype "passive"))
      (node (ref "U200") (pin "2") (pinfunction "LED2/~{INTSEL}_2") (pintype "bidirectional"))
    )
    (net (code "31") (name "Net-(U200-RBIAS)") (class "Default")
      (node (ref "R201") (pin "2") (pinfunction "2_2") (pintype "passive"))
      (node (ref "U200") (pin "24") (pinfunction "RBIAS_24") (pintype "bidirectional"))
    )
    (net (code "32") (name "Net-(U200-RXD0{slash}MODE0)") (class "Default")
      (node (ref "R209") (pin "1") (pinfunction "1_1") (pintype "passive"))
      (node (ref "U200") (pin "8") (pinfunction "RXD0/MODE0_8") (pintype "bidirectional"))
    )
    (net (code "33") (name "Net-(U200-RXD1{slash}MODE1)") (class "Default")
      (node (ref "R208") (pin "1") (pinfunction "1_1") (pintype "passive"))
      (node (ref "U200") (pin "7") (pinfunction "RXD1/MODE1_7") (pintype "bidirectional"))
    )
    (net (code "34") (name "Net-(U200-RXER{slash}PHYAD0)") (class "Default")
      (node (ref "R206") (pin "1") (pinfunction "1_1") (pintype "passive"))
      (node (ref "U200") (pin "10") (pinfunction "RXER/PHYAD0_10") (pintype "bidirectional"))
    )
    (net (code "35") (name "Net-(U200-VDDCR)") (class "Default")
      (node (ref "C201") (pin "1") (pinfunction "1_1") (pintype "passive"))
      (node (ref "U200") (pin "6") (pinfunction "VDDCR_6") (pintype "bidirectional"))
    )
    (net (code "36") (name "Net-(U200-XTAL1{slash}CLKIN)") (class "Default")
      (node (ref "R210") (pin "2") (pinfunction "2_2") (pintype "passive"))
      (node (ref "U200") (pin "5") (pinfunction "XTAL1/CLKIN_5") (pintype "bidirectional"))
    )
    (net (code "37") (name "Net-(U200-~{INT}{slash}REFCLKO)") (class "Default")
      (node (ref "R1") (pin "1") (pinfunction "1_1") (pintype "passive"))
      (node (ref "U200") (pin "14") (pinfunction "~{INT}/REFCLKO_14") (pintype "bidirectional"))
    )
    (net (code "38") (name "Net-(U300-OSCI)") (class "Default")
      (node (ref "Q300") (pin "2") (pinfunction "2_2") (pintype "passive"))
      (node (ref "U300") (pin "1") (pinfunction "OSCI_1") (pintype "bidirectional"))
    )
    (net (code "39") (name "Net-(U300-OSCO)") (class "Default")
      (node (ref "Q300") (pin "1") (pinfunction "1_1") (pintype "passive"))
      (node (ref "U300") (pin "2") (pinfunction "OSCO_2") (pintype "bidirectional"))
    )
    (net (code "40") (name "PROG_UART_RX") (class "Default")
      (node (ref "SV4") (pin "3") (pinfunction "3_3") (pintype "passive"))
      (node (ref "U100") (pin "34") (pinfunction "RXD0_34") (pintype "bidirectional"))
    )
    (net (code "41") (name "PROG_UART_TX") (class "Default")
      (node (ref "SV4") (pin "2") (pinfunction "2_2") (pintype "passive"))
      (node (ref "U100") (pin "35") (pinfunction "TXD0_35") (pintype "bidirectional"))
    )
    (net (code "42") (name "PWR_GATE") (class "Default")
      (node (ref "R8") (pin "2") (pinfunction "2_2") (pintype "passive"))
      (node (ref "U1") (pin "4") (pinfunction "ON_4") (pintype "bidirectional"))
      (node (ref "U100") (pin "26") (pinfunction "IO4_26") (pintype "bidirectional"))
    )
    (net (code "43") (name "RTC_INT") (class "Default")
      (node (ref "R301") (pin "1") (pinfunction "1_1") (pintype "passive"))
      (node (ref "U300") (pin "3") (pinfunction "~{INT}_3") (pintype "bidirectional"))
    )
    (net (code "44") (name "RTS") (class "Default")
      (node (ref "Q2") (pin "2") (pinfunction "E_2") (pintype "passive"))
      (node (ref "R13") (pin "2") (pinfunction "2_2") (pintype "passive"))
      (node (ref "SV4") (pin "5") (pinfunction "5_5") (pintype "passive"))
    )
    (net (code "45") (name "RXD0") (class "Default")
      (node (ref "R209") (pin "2") (pinfunction "2_2") (pintype "passive"))
      (node (ref "U100") (pin "10") (pinfunction "IO25_10") (pintype "bidirectional"))
    )
    (net (code "46") (name "RXD1") (class "Default")
      (node (ref "R208") (pin "2") (pinfunction "2_2") (pintype "passive"))
      (node (ref "U100") (pin "11") (pinfunction "IO26_11") (pintype "bidirectional"))
    )
    (net (code "47") (name "RX_N") (class "Default")
      (node (ref "J1") (pin "6") (pinfunction "RD-_6") (pintype "bidirectional"))
      (node (ref "R5") (pin "2") (pinfunction "2_2") (pintype "passive"))
      (node (ref "U200") (pin "22") (pinfunction "RXN_22") (pintype "bidirectional"))
    )
    (net (code "48") (name "RX_P") (class "Default")
      (node (ref "J1") (pin "3") (pinfunction "RD+_3") (pintype "bidirectional"))
      (node (ref "R4") (pin "2") (pinfunction "2_2") (pintype "passive"))
      (node (ref "U200") (pin "23") (pinfunction "RXP_23") (pintype "bidirectional"))
    )
    (net (code "49") (name "TXD0") (class "Default")
      (node (ref "U100") (pin "31") (pinfunction "IO19_31") (pintype "bidirectional"))
      (node (ref "U200") (pin "17") (pinfunction "TXD0_17") (pintype "bidirectional"))
    )
    (net (code "50") (name "TXD1") (class "Default")
      (node (ref "U100") (pin "36") (pinfunction "IO22_36") (pintype "bidirectional"))
      (node (ref "U200") (pin "18") (pinfunction "TXD1_18") (pintype "bidirectional"))
    )
    (net (code "51") (name "TX_EN") (class "Default")
      (node (ref "U100") (pin "33") (pinfunction "IO21_33") (pintype "bidirectional"))
      (node (ref "U200") (pin "16") (pinfunction "TXEN_16") (pintype "bidirectional"))
    )
    (net (code "52") (name "TX_N") (class "Default")
      (node (ref "J1") (pin "2") (pinfunction "TD-_2") (pintype "bidirectional"))
      (node (ref "R3") (pin "2") (pinfunction "2_2") (pintype "passive"))
      (node (ref "U200") (pin "20") (pinfunction "TXN_20") (pintype "bidirectional"))
    )
    (net (code "53") (name "TX_P") (class "Default")
      (node (ref "J1") (pin "1") (pinfunction "TD+_1") (pintype "bidirectional"))
      (node (ref "R2") (pin "2") (pinfunction "2_2") (pintype "passive"))
      (node (ref "U200") (pin "21") (pinfunction "TXP_21") (pintype "bidirectional"))
    )
    (net (code "54") (name "UART1_RX") (class "Default")
      (node (ref "SV1") (pin "10") (pinfunction "10_10") (pintype "passive"))
    )
    (net (code "55") (name "UART1_TX") (class "Default")
      (node (ref "SV1") (pin "8") (pinfunction "8_8") (pintype "passive"))
    )
    (net (code "56") (name "UART_BOARD_RX") (class "Default")
      (node (ref "SV3") (pin "2") (pinfunction "2_2") (pintype "passive"))
      (node (ref "U100") (pin "9") (pinfunction "IO33_9") (pintype "bidirectional"))
    )
    (net (code "57") (name "UART_BOARD_TX") (class "Default")
      (node (ref "SV3") (pin "3") (pinfunction "3_3") (pintype "passive"))
      (node (ref "U100") (pin "8") (pinfunction "IO32_8") (pintype "bidirectional"))
    )
    (net (code "58") (name "USB_VBUS") (class "Default")
      (node (ref "SV2") (pin "1") (pinfunction "1_1") (pintype "passive"))
      (node (ref "SV2") (pin "2") (pinfunction "2_2") (pintype "passive"))
    )
    (net (code "59") (name "VDD_LAN") (class "Default")
      (node (ref "C2") (pin "1") (pinfunction "1_1") (pintype "passive"))
      (node (ref "C202") (pin "1") (pinfunction "1_1") (pintype "passive"))
      (node (ref "C203") (pin "1") (pinfunction "1_1") (pintype "passive"))
      (node (ref "J1") (pin "4") (pinfunction "TXCT_4") (pintype "bidirectional"))
      (node (ref "J1") (pin "5") (pinfunction "RXCT_5") (pintype "bidirectional"))
      (node (ref "J1") (pin "GRNA") (pinfunction "GRNA_GRNA") (pintype "bidirectional"))
      (node (ref "J1") (pin "YLWA") (pinfunction "YELA_YLWA") (pintype "bidirectional"))
      (node (ref "L1") (pin "2") (pinfunction "2_2") (pintype "passive"))
      (node (ref "R2") (pin "1") (pinfunction "1_1") (pintype "passive"))
      (node (ref "R3") (pin "1") (pinfunction "1_1") (pintype "passive"))
      (node (ref "R4") (pin "1") (pinfunction "1_1") (pintype "passive"))
      (node (ref "R5") (pin "1") (pinfunction "1_1") (pintype "passive"))
      (node (ref "U200") (pin "1") (pinfunction "VDD2A_1") (pintype "bidirectional"))
      (node (ref "U200") (pin "19") (pinfunction "VDD1A_19") (pintype "bidirectional"))
    )
    (net (code "60") (name "unconnected-(J1-NC-Pad7)") (class "Default")
      (node (ref "J1") (pin "7") (pinfunction "NC_7") (pintype "bidirectional"))
    )
    (net (code "61") (name "unconnected-(SV1-Pad1)") (class "Default")
      (node (ref "SV1") (pin "1") (pinfunction "1_1") (pintype "passive"))
    )
    (net (code "62") (name "unconnected-(SV1-Pad7)") (class "Default")
      (node (ref "SV1") (pin "7") (pinfunction "7_7") (pintype "passive"))
    )
    (net (code "63") (name "unconnected-(SV1-Pad11)") (class "Default")
      (node (ref "SV1") (pin "11") (pinfunction "11_11") (pintype "passive"))
    )
    (net (code "64") (name "unconnected-(SV1-Pad12)") (class "Default")
      (node (ref "SV1") (pin "12") (pinfunction "12_12") (pintype "passive"))
    )
    (net (code "65") (name "unconnected-(SV1-Pad13)") (class "Default")
      (node (ref "SV1") (pin "13") (pinfunction "13_13") (pintype "passive"))
    )
    (net (code "66") (name "unconnected-(SV1-Pad15)") (class "Default")
      (node (ref "SV1") (pin "15") (pinfunction "15_15") (pintype "passive"))
    )
    (net (code "67") (name "unconnected-(SV1-Pad16)") (class "Default")
      (node (ref "SV1") (pin "16") (pinfunction "16_16") (pintype "passive"))
    )
    (net (code "68") (name "unconnected-(SV1-Pad17)") (class "Default")
      (node (ref "SV1") (pin "17") (pinfunction "17_17") (pintype "passive"))
    )
    (net (code "69") (name "unconnected-(SV1-Pad18)") (class "Default")
      (node (ref "SV1") (pin "18") (pinfunction "18_18") (pintype "passive"))
    )
    (net (code "70") (name "unconnected-(SV1-Pad19)") (class "Default")
      (node (ref "SV1") (pin "19") (pinfunction "19_19") (pintype "passive"))
    )
    (net (code "71") (name "unconnected-(SV1-Pad21)") (class "Default")
      (node (ref "SV1") (pin "21") (pinfunction "21_21") (pintype "passive"))
    )
    (net (code "72") (name "unconnected-(SV1-Pad22)") (class "Default")
      (node (ref "SV1") (pin "22") (pinfunction "22_22") (pintype "passive"))
    )
    (net (code "73") (name "unconnected-(SV1-Pad23)") (class "Default")
      (node (ref "SV1") (pin "23") (pinfunction "23_23") (pintype "passive"))
    )
    (net (code "74") (name "unconnected-(SV1-Pad24)") (class "Default")
      (node (ref "SV1") (pin "24") (pinfunction "24_24") (pintype "passive"))
    )
    (net (code "75") (name "unconnected-(SV1-Pad26)") (class "Default")
      (node (ref "SV1") (pin "26") (pinfunction "26_26") (pintype "passive"))
    )
    (net (code "76") (name "unconnected-(SV2-Pad3)") (class "Default")
      (node (ref "SV2") (pin "3") (pinfunction "3_3") (pintype "passive"))
    )
    (net (code "77") (name "unconnected-(SV2-Pad4)") (class "Default")
      (node (ref "SV2") (pin "4") (pinfunction "4_4") (pintype "passive"))
    )
    (net (code "78") (name "unconnected-(SV2-Pad5)") (class "Default")
      (node (ref "SV2") (pin "5") (pinfunction "5_5") (pintype "passive"))
    )
    (net (code "79") (name "unconnected-(SV2-Pad6)") (class "Default")
      (node (ref "SV2") (pin "6") (pinfunction "6_6") (pintype "passive"))
    )
    (net (code "80") (name "unconnected-(U100-IO5-Pad29)") (class "Default")
      (node (ref "U100") (pin "29") (pinfunction "IO5_29") (pintype "bidirectional"))
    )
    (net (code "81") (name "unconnected-(U100-IO12-Pad14)") (class "Default")
      (node (ref "U100") (pin "14") (pinfunction "IO12_14") (pintype "bidirectional"))
    )
    (net (code "82") (name "unconnected-(U100-IO35-Pad7)") (class "Default")
      (node (ref "U100") (pin "7") (pinfunction "IO35_7") (pintype "input"))
    )
    (net (code "83") (name "unconnected-(U100-SCK{slash}CLK-Pad20)") (class "Default")
      (node (ref "U100") (pin "20") (pinfunction "SCK/CLK_20") (pintype "bidirectional"))
    )
    (net (code "84") (name "unconnected-(U100-SCS{slash}CMD-Pad19)") (class "Default")
      (node (ref "U100") (pin "19") (pinfunction "SCS/CMD_19") (pintype "bidirectional"))
    )
    (net (code "85") (name "unconnected-(U100-SDI{slash}SD1-Pad22)") (class "Default")
      (node (ref "U100") (pin "22") (pinfunction "SDI/SD1_22") (pintype "bidirectional"))
    )
    (net (code "86") (name "unconnected-(U100-SDO{slash}SD0-Pad21)") (class "Default")
      (node (ref "U100") (pin "21") (pinfunction "SDO/SD0_21") (pintype "bidirectional"))
    )
    (net (code "87") (name "unconnected-(U100-SENSOR_VN-Pad5)") (class "Default")
      (node (ref "U100") (pin "5") (pinfunction "SENSOR_VN_5") (pintype "input"))
    )
    (net (code "88") (name "unconnected-(U100-SENSOR_VP-Pad4)") (class "Default")
      (node (ref "U100") (pin "4") (pinfunction "SENSOR_VP_4") (pintype "input"))
    )
    (net (code "89") (name "unconnected-(U100-SHD{slash}SD2-Pad17)") (class "Default")
      (node (ref "U100") (pin "17") (pinfunction "SHD/SD2_17") (pintype "bidirectional"))
    )
    (net (code "90") (name "unconnected-(U100-SWP{slash}SD3-Pad18)") (class "Default")
      (node (ref "U100") (pin "18") (pinfunction "SWP/SD3_18") (pintype "bidirectional"))
    )
    (net (code "91") (name "unconnected-(U200-XTAL2-Pad4)") (class "Default")
      (node (ref "U200") (pin "4") (pinfunction "XTAL2_4") (pintype "bidirectional"))
    )
    (net (code "92") (name "unconnected-(U300-CLKOUT-Pad7)") (class "Default")
      (node (ref "U300") (pin "7") (pinfunction "CLKOUT_7") (pintype "bidirectional"))
    )
    (net (code "93") (name "~{RST}") (class "Default")
      (node (ref "C211") (pin "1") (pinfunction "1_1") (pintype "passive"))
      (node (ref "R211") (pin "1") (pinfunction "1_1") (pintype "passive"))
      (node (ref "U200") (pin "15") (pinfunction "~{RST}_15") (pintype "bidirectional"))
    )
  )
)
